# v0_9.net
KiCad netlist of a schematic drawn in EAGLE
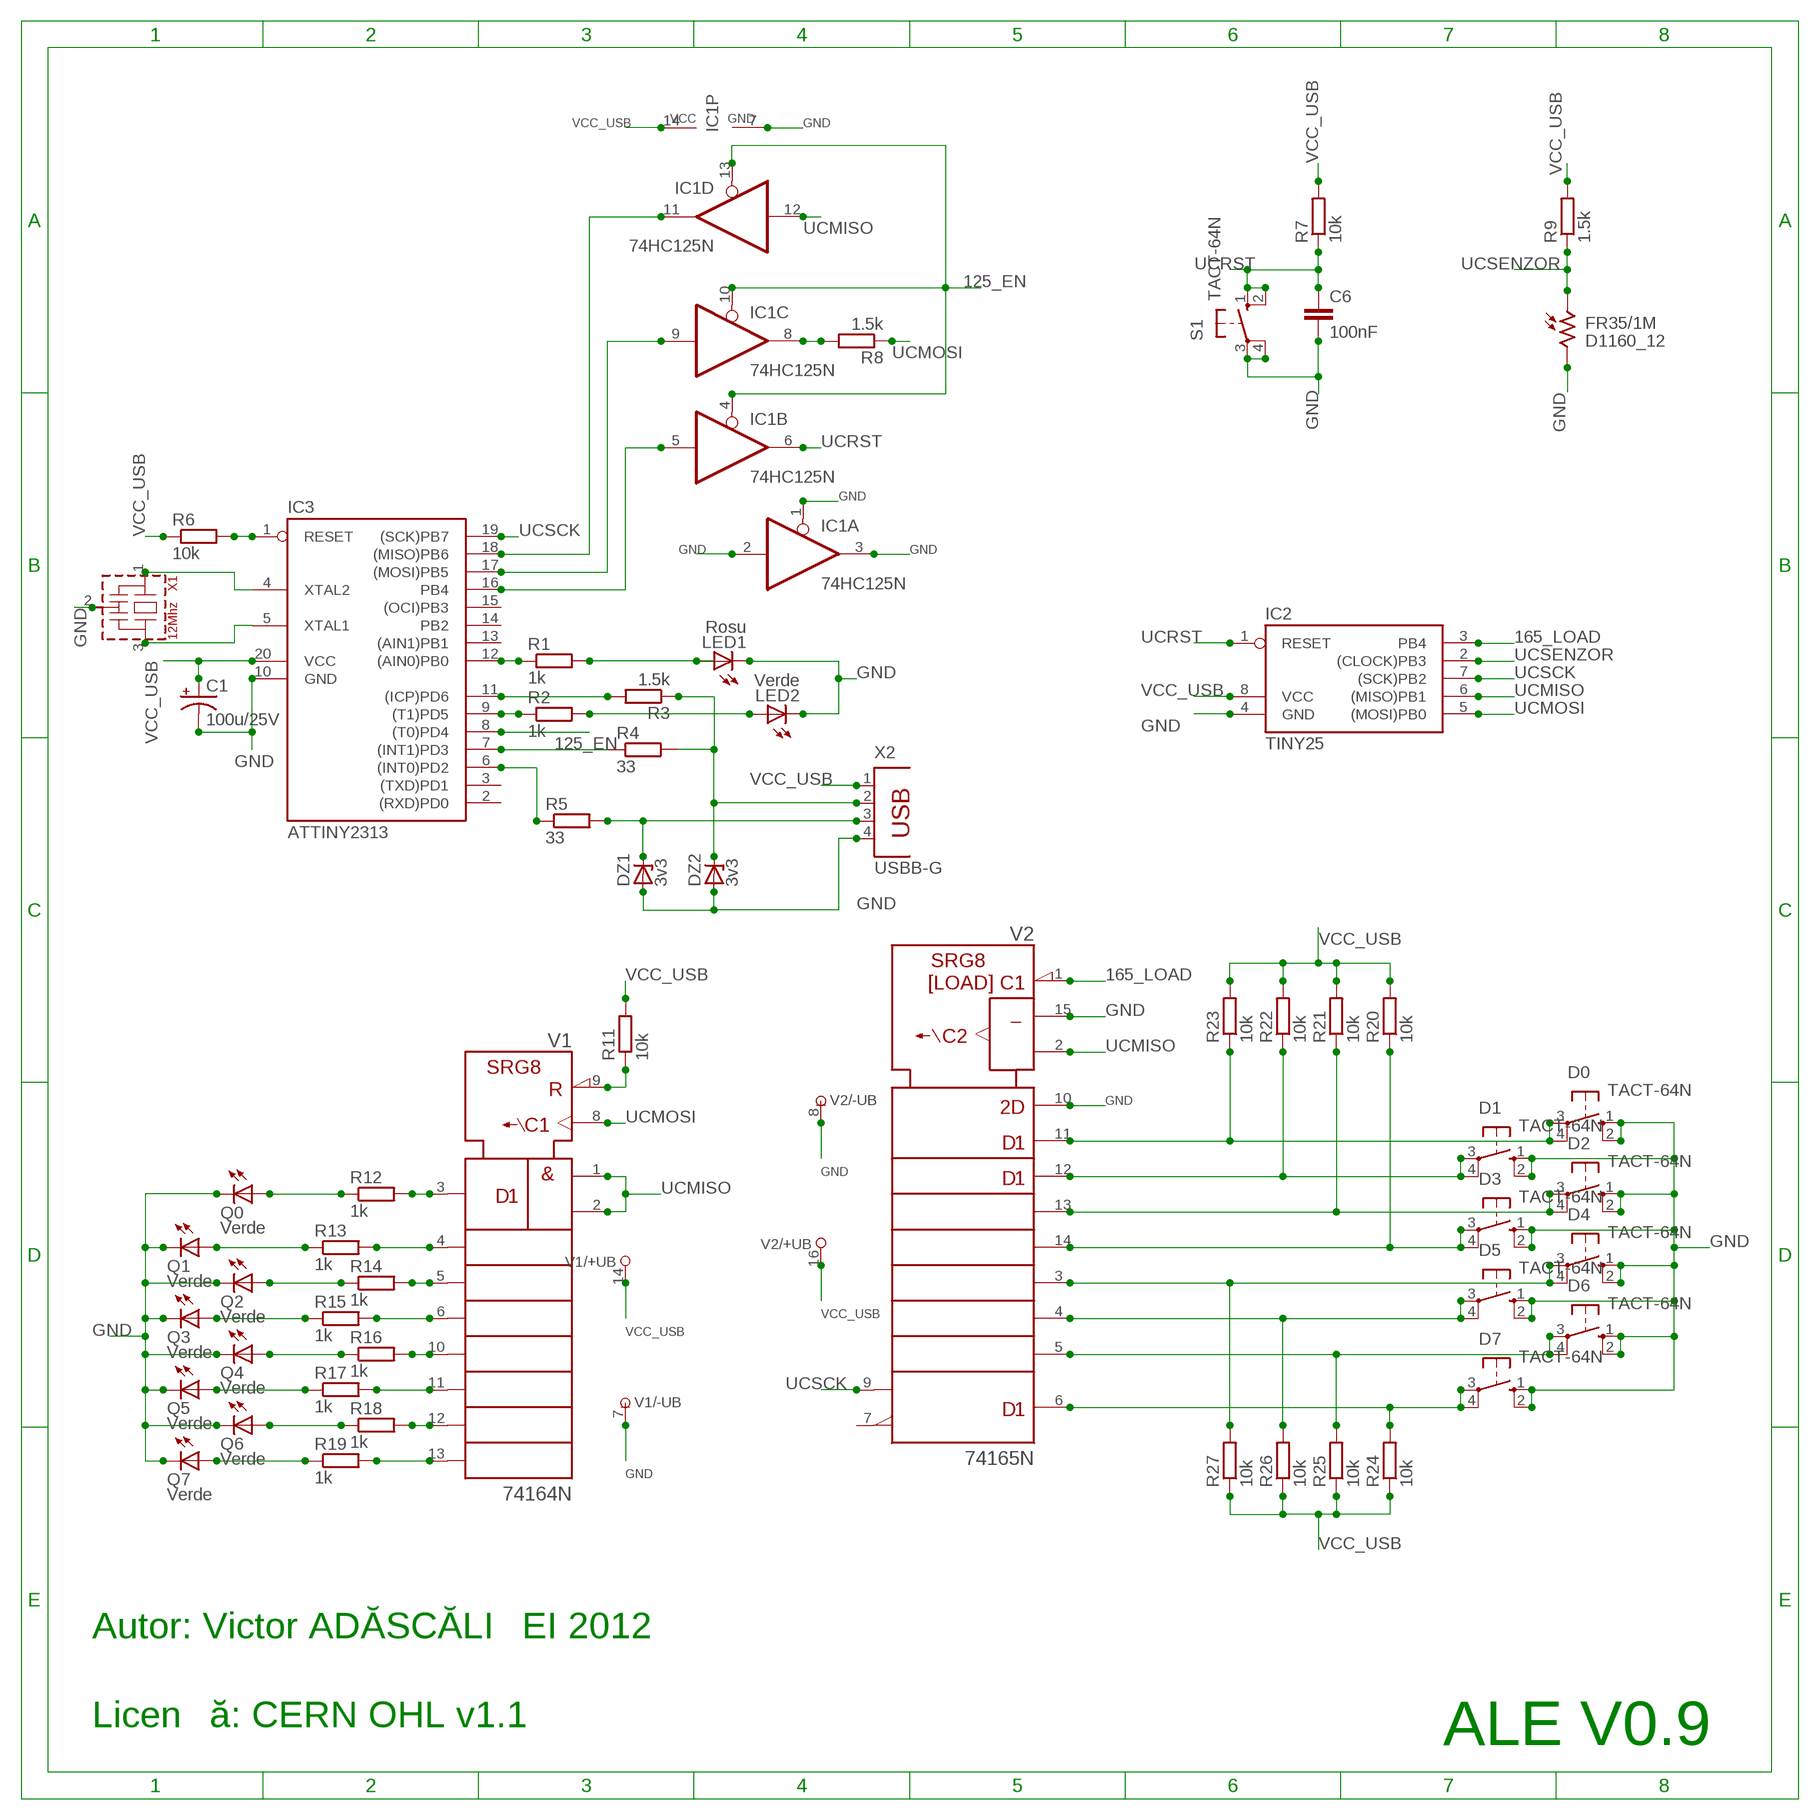
[diagram p0: schematic, sheet 1]

(export (version "E")
  (design (tool "Eeschema 10.0.6"))
  (components
    (comp (ref "C1")
      (value "100u/25V")
      (footprint "eagle-import:E2,5-6")
      (libsource (lib "eagle-import") (part "CPOL-USE2.5-6"))
    )
    (comp (ref "C6")
      (value "100nF")
      (footprint "eagle-import:C050-025X075")
      (libsource (lib "eagle-import") (part "C-EU050-025X075"))
    )
    (comp (ref "D0")
      (value "TACT-64N")
      (footprint "eagle-import:B3F-10XX")
      (libsource (lib "eagle-import") (part "10-XX"))
    )
    (comp (ref "D1")
      (value "TACT-64N")
      (footprint "eagle-import:B3F-10XX")
      (libsource (lib "eagle-import") (part "10-XX"))
    )
    (comp (ref "D2")
      (value "TACT-64N")
      (footprint "eagle-import:B3F-10XX")
      (libsource (lib "eagle-import") (part "10-XX"))
    )
    (comp (ref "D3")
      (value "TACT-64N")
      (footprint "eagle-import:B3F-10XX")
      (libsource (lib "eagle-import") (part "10-XX"))
    )
    (comp (ref "D4")
      (value "TACT-64N")
      (footprint "eagle-import:B3F-10XX")
      (libsource (lib "eagle-import") (part "10-XX"))
    )
    (comp (ref "D5")
      (value "TACT-64N")
      (footprint "eagle-import:B3F-10XX")
      (libsource (lib "eagle-import") (part "10-XX"))
    )
    (comp (ref "D6")
      (value "TACT-64N")
      (footprint "eagle-import:B3F-10XX")
      (libsource (lib "eagle-import") (part "10-XX"))
    )
    (comp (ref "D7")
      (value "TACT-64N")
      (footprint "eagle-import:B3F-10XX")
      (libsource (lib "eagle-import") (part "10-XX"))
    )
    (comp (ref "DZ1")
      (value "3v3")
      (footprint "eagle-import:ZDIO-7.5")
      (libsource (lib "eagle-import") (part "ZENER-DIODEZD-7.5"))
    )
    (comp (ref "DZ2")
      (value "3v3")
      (footprint "eagle-import:ZDIO-7.5")
      (libsource (lib "eagle-import") (part "ZENER-DIODEZD-7.5"))
    )
    (comp (ref "FR35/1M")
      (value "D1160_12")
      (footprint "eagle-import:D11XX")
      (libsource (lib "eagle-import") (part "D1160_12"))
    )
    (comp (ref "IC1")
      (value "74HC125N")
      (footprint "eagle-import:DIL14")
      (libsource (lib "eagle-import") (part "74125NAC"))
    )
    (comp (ref "IC2")
      (value "TINY25")
      (footprint "eagle-import:DIL08")
      (libsource (lib "eagle-import") (part "TINY22P"))
    )
    (comp (ref "IC3")
      (value "ATTINY2313")
      (footprint "eagle-import:DIL20")
      (libsource (lib "eagle-import") (part "AT90S2313P"))
    )
    (comp (ref "LED1")
      (value "Rosu")
      (footprint "eagle-import:LED3MM")
      (libsource (lib "eagle-import") (part "LED3MM"))
    )
    (comp (ref "LED2")
      (value "Verde")
      (footprint "eagle-import:LED3MM")
      (libsource (lib "eagle-import") (part "LED3MM"))
    )
    (comp (ref "Q0")
      (value "Verde")
      (footprint "eagle-import:LED3MM")
      (libsource (lib "eagle-import") (part "LED3MM"))
    )
    (comp (ref "Q1")
      (value "Verde")
      (footprint "eagle-import:LED3MM")
      (libsource (lib "eagle-import") (part "LED3MM"))
    )
    (comp (ref "Q2")
      (value "Verde")
      (footprint "eagle-import:LED3MM")
      (libsource (lib "eagle-import") (part "LED3MM"))
    )
    (comp (ref "Q3")
      (value "Verde")
      (footprint "eagle-import:LED3MM")
      (libsource (lib "eagle-import") (part "LED3MM"))
    )
    (comp (ref "Q4")
      (value "Verde")
      (footprint "eagle-import:LED3MM")
      (libsource (lib "eagle-import") (part "LED3MM"))
    )
    (comp (ref "Q5")
      (value "Verde")
      (footprint "eagle-import:LED3MM")
      (libsource (lib "eagle-import") (part "LED3MM"))
    )
    (comp (ref "Q6")
      (value "Verde")
      (footprint "eagle-import:LED3MM")
      (libsource (lib "eagle-import") (part "LED3MM"))
    )
    (comp (ref "Q7")
      (value "Verde")
      (footprint "eagle-import:LED3MM")
      (libsource (lib "eagle-import") (part "LED3MM"))
    )
    (comp (ref "R1")
      (value "1k")
      (footprint "eagle-import:0207_10")
      (libsource (lib "eagle-import") (part "R-EU_0207/10"))
    )
    (comp (ref "R2")
      (value "1k")
      (footprint "eagle-import:0204_5")
      (libsource (lib "eagle-import") (part "R-EU_0204/5"))
    )
    (comp (ref "R3")
      (value "1.5k")
      (footprint "eagle-import:0207_10")
      (libsource (lib "eagle-import") (part "R-EU_0207/10"))
    )
    (comp (ref "R4")
      (value "33")
      (footprint "eagle-import:0207_12")
      (libsource (lib "eagle-import") (part "R-EU_0207/12"))
    )
    (comp (ref "R5")
      (value "33")
      (footprint "eagle-import:0207_10")
      (libsource (lib "eagle-import") (part "R-EU_0207/10"))
    )
    (comp (ref "R6")
      (value "10k")
      (footprint "eagle-import:0207_10")
      (libsource (lib "eagle-import") (part "R-EU_0207/10"))
    )
    (comp (ref "R7")
      (value "10k")
      (footprint "eagle-import:0204_7")
      (libsource (lib "eagle-import") (part "R-EU_0204/7"))
    )
    (comp (ref "R8")
      (value "1.5k")
      (footprint "eagle-import:0207_10")
      (libsource (lib "eagle-import") (part "R-EU_0207/10"))
    )
    (comp (ref "R9")
      (value "1.5k")
      (footprint "eagle-import:0207_12")
      (libsource (lib "eagle-import") (part "R-EU_0207/12"))
    )
    (comp (ref "R11")
      (value "10k")
      (footprint "eagle-import:0207_15")
      (libsource (lib "eagle-import") (part "R-EU_0207/15"))
    )
    (comp (ref "R12")
      (value "1k")
      (footprint "eagle-import:0207_10")
      (libsource (lib "eagle-import") (part "R-EU_0207/10"))
    )
    (comp (ref "R13")
      (value "1k")
      (footprint "eagle-import:0207_10")
      (libsource (lib "eagle-import") (part "R-EU_0207/10"))
    )
    (comp (ref "R14")
      (value "1k")
      (footprint "eagle-import:0207_10")
      (libsource (lib "eagle-import") (part "R-EU_0207/10"))
    )
    (comp (ref "R15")
      (value "1k")
      (footprint "eagle-import:0207_10")
      (libsource (lib "eagle-import") (part "R-EU_0207/10"))
    )
    (comp (ref "R16")
      (value "1k")
      (footprint "eagle-import:0207_10")
      (libsource (lib "eagle-import") (part "R-EU_0207/10"))
    )
    (comp (ref "R17")
      (value "1k")
      (footprint "eagle-import:0207_10")
      (libsource (lib "eagle-import") (part "R-EU_0207/10"))
    )
    (comp (ref "R18")
      (value "1k")
      (footprint "eagle-import:0207_10")
      (libsource (lib "eagle-import") (part "R-EU_0207/10"))
    )
    (comp (ref "R19")
      (value "1k")
      (footprint "eagle-import:0207_10")
      (libsource (lib "eagle-import") (part "R-EU_0207/10"))
    )
    (comp (ref "R20")
      (value "10k")
      (footprint "eagle-import:0207_10")
      (libsource (lib "eagle-import") (part "R-EU_0207/10"))
    )
    (comp (ref "R21")
      (value "10k")
      (footprint "eagle-import:0207_10")
      (libsource (lib "eagle-import") (part "R-EU_0207/10"))
    )
    (comp (ref "R22")
      (value "10k")
      (footprint "eagle-import:0204_7")
      (libsource (lib "eagle-import") (part "R-EU_0204/7"))
    )
    (comp (ref "R23")
      (value "10k")
      (footprint "eagle-import:0204_7")
      (libsource (lib "eagle-import") (part "R-EU_0204/7"))
    )
    (comp (ref "R24")
      (value "10k")
      (footprint "eagle-import:0207_10")
      (libsource (lib "eagle-import") (part "R-EU_0207/10"))
    )
    (comp (ref "R25")
      (value "10k")
      (footprint "eagle-import:0207_10")
      (libsource (lib "eagle-import") (part "R-EU_0207/10"))
    )
    (comp (ref "R26")
      (value "10k")
      (footprint "eagle-import:0207_10")
      (libsource (lib "eagle-import") (part "R-EU_0207/10"))
    )
    (comp (ref "R27")
      (value "10k")
      (footprint "eagle-import:0207_10")
      (libsource (lib "eagle-import") (part "R-EU_0207/10"))
    )
    (comp (ref "S1")
      (value "TACT-64N")
      (footprint "eagle-import:B3F-10XX")
      (libsource (lib "eagle-import") (part "10-XX"))
    )
    (comp (ref "V1")
      (value "74164N")
      (footprint "eagle-import:DIL14")
      (libsource (lib "eagle-import") (part "74164N"))
    )
    (comp (ref "V2")
      (value "74165N")
      (footprint "eagle-import:DIL16")
      (libsource (lib "eagle-import") (part "74165N"))
    )
    (comp (ref "X1")
      (value "12Mhz")
      (footprint "eagle-import:CSTLS_X")
      (libsource (lib "eagle-import") (part "CSTLS_X"))
    )
    (comp (ref "X2")
      (value "USBB-G")
      (footprint "eagle-import:PN61729")
      (libsource (lib "eagle-import") (part "PN61729"))
    )
  )
  (nets
    (net (code "1") (name "/125_EN") (class "Default")
      (node (ref "IC1") (pin "10") (pinfunction "OE_10") (pintype "input"))
      (node (ref "IC1") (pin "13") (pinfunction "OE_13") (pintype "input"))
      (node (ref "IC1") (pin "4") (pinfunction "OE_4") (pintype "input"))
      (node (ref "IC3") (pin "8") (pinfunction "(T0)PD4_8") (pintype "bidirectional"))
    )
    (net (code "2") (name "/165_LOAD") (class "Default")
      (node (ref "IC2") (pin "3") (pinfunction "PB4_3") (pintype "bidirectional"))
      (node (ref "V2") (pin "1") (pinfunction "SH/~{LD}_1") (pintype "input"))
    )
    (net (code "3") (name "/GND") (class "Default")
      (node (ref "C1") (pin "-") (pinfunction "-_-") (pintype "passive"))
      (node (ref "C6") (pin "2") (pinfunction "2_2") (pintype "passive"))
      (node (ref "D0") (pin "1") (pinfunction "S_1") (pintype "passive"))
      (node (ref "D0") (pin "2") (pinfunction "S1_2") (pintype "passive"))
      (node (ref "D1") (pin "1") (pinfunction "S_1") (pintype "passive"))
      (node (ref "D1") (pin "2") (pinfunction "S1_2") (pintype "passive"))
      (node (ref "D2") (pin "1") (pinfunction "S_1") (pintype "passive"))
      (node (ref "D2") (pin "2") (pinfunction "S1_2") (pintype "passive"))
      (node (ref "D3") (pin "1") (pinfunction "S_1") (pintype "passive"))
      (node (ref "D3") (pin "2") (pinfunction "S1_2") (pintype "passive"))
      (node (ref "D4") (pin "1") (pinfunction "S_1") (pintype "passive"))
      (node (ref "D4") (pin "2") (pinfunction "S1_2") (pintype "passive"))
      (node (ref "D5") (pin "1") (pinfunction "S_1") (pintype "passive"))
      (node (ref "D5") (pin "2") (pinfunction "S1_2") (pintype "passive"))
      (node (ref "D6") (pin "1") (pinfunction "S_1") (pintype "passive"))
      (node (ref "D6") (pin "2") (pinfunction "S1_2") (pintype "passive"))
      (node (ref "D7") (pin "1") (pinfunction "S_1") (pintype "passive"))
      (node (ref "D7") (pin "2") (pinfunction "S1_2") (pintype "passive"))
      (node (ref "DZ1") (pin "A") (pinfunction "A_A") (pintype "passive"))
      (node (ref "DZ2") (pin "A") (pinfunction "A_A") (pintype "passive"))
      (node (ref "FR35/1M") (pin "2") (pinfunction "2_2") (pintype "passive"))
      (node (ref "IC1") (pin "1") (pinfunction "OE_1") (pintype "input"))
      (node (ref "IC1") (pin "2") (pinfunction "I_2") (pintype "input"))
      (node (ref "IC1") (pin "3") (pinfunction "O_3") (pintype "tri_state"))
      (node (ref "IC1") (pin "7") (pinfunction "GND_7") (pintype "power_in"))
      (node (ref "IC2") (pin "4") (pinfunction "GND_4") (pintype "power_in"))
      (node (ref "IC3") (pin "10") (pinfunction "GND_10") (pintype "power_in"))
      (node (ref "LED1") (pin "K") (pinfunction "C_K") (pintype "passive"))
      (node (ref "LED2") (pin "K") (pinfunction "C_K") (pintype "passive"))
      (node (ref "Q0") (pin "K") (pinfunction "C_K") (pintype "passive"))
      (node (ref "Q1") (pin "K") (pinfunction "C_K") (pintype "passive"))
      (node (ref "Q2") (pin "K") (pinfunction "C_K") (pintype "passive"))
      (node (ref "Q3") (pin "K") (pinfunction "C_K") (pintype "passive"))
      (node (ref "Q4") (pin "K") (pinfunction "C_K") (pintype "passive"))
      (node (ref "Q5") (pin "K") (pinfunction "C_K") (pintype "passive"))
      (node (ref "Q6") (pin "K") (pinfunction "C_K") (pintype "passive"))
      (node (ref "Q7") (pin "K") (pinfunction "C_K") (pintype "passive"))
      (node (ref "S1") (pin "3") (pinfunction "P_3") (pintype "passive"))
      (node (ref "S1") (pin "4") (pinfunction "P1_4") (pintype "passive"))
      (node (ref "V1") (pin "7") (pinfunction "-UB_7") (pintype "power_in"))
      (node (ref "V2") (pin "10") (pinfunction "SER_10") (pintype "input"))
      (node (ref "V2") (pin "15") (pinfunction "CLK_INH_15") (pintype "input"))
      (node (ref "V2") (pin "8") (pinfunction "-UB_8") (pintype "power_in"))
      (node (ref "X1") (pin "2") (pinfunction "VSS_2") (pintype "power_in"))
      (node (ref "X2") (pin "4") (pinfunction "4_4") (pintype "passive"))
    )
    (net (code "4") (name "/UCMISO") (class "Default")
      (node (ref "IC1") (pin "12") (pinfunction "I_12") (pintype "input"))
      (node (ref "IC2") (pin "6") (pinfunction "(MISO)PB1_6") (pintype "bidirectional"))
      (node (ref "V1") (pin "1") (pinfunction "A_1") (pintype "input"))
      (node (ref "V1") (pin "2") (pinfunction "B_2") (pintype "input"))
      (node (ref "V2") (pin "2") (pinfunction "CLK_2") (pintype "input"))
    )
    (net (code "5") (name "/UCMOSI") (class "Default")
      (node (ref "IC2") (pin "5") (pinfunction "(MOSI)PB0_5") (pintype "bidirectional"))
      (node (ref "R8") (pin "1") (pinfunction "1_1") (pintype "passive"))
      (node (ref "V1") (pin "8") (pinfunction "CLK_8") (pintype "input"))
    )
    (net (code "6") (name "/UCRST") (class "Default")
      (node (ref "C6") (pin "1") (pinfunction "1_1") (pintype "passive"))
      (node (ref "IC1") (pin "6") (pinfunction "O_6") (pintype "tri_state"))
      (node (ref "IC2") (pin "1") (pinfunction "RESET_1") (pintype "input"))
      (node (ref "R7") (pin "1") (pinfunction "1_1") (pintype "passive"))
      (node (ref "S1") (pin "1") (pinfunction "S_1") (pintype "passive"))
      (node (ref "S1") (pin "2") (pinfunction "S1_2") (pintype "passive"))
    )
    (net (code "7") (name "/UCSCK") (class "Default")
      (node (ref "IC2") (pin "7") (pinfunction "(SCK)PB2_7") (pintype "bidirectional"))
      (node (ref "IC3") (pin "19") (pinfunction "(SCK)PB7_19") (pintype "bidirectional"))
      (node (ref "V2") (pin "9") (pinfunction "QH_9") (pintype "output"))
    )
    (net (code "8") (name "/UCSENZOR") (class "Default")
      (node (ref "FR35/1M") (pin "1") (pinfunction "1_1") (pintype "passive"))
      (node (ref "IC2") (pin "2") (pinfunction "(CLOCK)PB3_2") (pintype "bidirectional"))
      (node (ref "R9") (pin "1") (pinfunction "1_1") (pintype "passive"))
    )
    (net (code "9") (name "/VCC_USB") (class "Default")
      (node (ref "C1") (pin "+") (pinfunction "+_+") (pintype "passive"))
      (node (ref "IC1") (pin "14") (pinfunction "VCC_14") (pintype "power_in"))
      (node (ref "IC2") (pin "8") (pinfunction "VCC_8") (pintype "power_in"))
      (node (ref "IC3") (pin "20") (pinfunction "VCC_20") (pintype "power_in"))
      (node (ref "R11") (pin "2") (pinfunction "2_2") (pintype "passive"))
      (node (ref "R20") (pin "2") (pinfunction "2_2") (pintype "passive"))
      (node (ref "R21") (pin "2") (pinfunction "2_2") (pintype "passive"))
      (node (ref "R22") (pin "2") (pinfunction "2_2") (pintype "passive"))
      (node (ref "R23") (pin "2") (pinfunction "2_2") (pintype "passive"))
      (node (ref "R24") (pin "1") (pinfunction "1_1") (pintype "passive"))
      (node (ref "R25") (pin "1") (pinfunction "1_1") (pintype "passive"))
      (node (ref "R26") (pin "1") (pinfunction "1_1") (pintype "passive"))
      (node (ref "R27") (pin "1") (pinfunction "1_1") (pintype "passive"))
      (node (ref "R6") (pin "1") (pinfunction "1_1") (pintype "passive"))
      (node (ref "R7") (pin "2") (pinfunction "2_2") (pintype "passive"))
      (node (ref "R9") (pin "2") (pinfunction "2_2") (pintype "passive"))
      (node (ref "V1") (pin "14") (pinfunction "+UB_14") (pintype "power_in"))
      (node (ref "V2") (pin "16") (pinfunction "+UB_16") (pintype "power_in"))
      (node (ref "X2") (pin "1") (pinfunction "1_1") (pintype "passive"))
    )
    (net (code "10") (name "Net-(D0-P)") (class "Default")
      (node (ref "D0") (pin "3") (pinfunction "P_3") (pintype "passive"))
      (node (ref "D0") (pin "4") (pinfunction "P1_4") (pintype "passive"))
      (node (ref "R23") (pin "1") (pinfunction "1_1") (pintype "passive"))
      (node (ref "V2") (pin "11") (pinfunction "A_11") (pintype "input"))
    )
    (net (code "11") (name "Net-(D1-P)") (class "Default")
      (node (ref "D1") (pin "3") (pinfunction "P_3") (pintype "passive"))
      (node (ref "D1") (pin "4") (pinfunction "P1_4") (pintype "passive"))
      (node (ref "R22") (pin "1") (pinfunction "1_1") (pintype "passive"))
      (node (ref "V2") (pin "12") (pinfunction "B_12") (pintype "input"))
    )
    (net (code "12") (name "Net-(D2-P)") (class "Default")
      (node (ref "D2") (pin "3") (pinfunction "P_3") (pintype "passive"))
      (node (ref "D2") (pin "4") (pinfunction "P1_4") (pintype "passive"))
      (node (ref "R21") (pin "1") (pinfunction "1_1") (pintype "passive"))
      (node (ref "V2") (pin "13") (pinfunction "C_13") (pintype "input"))
    )
    (net (code "13") (name "Net-(D3-P)") (class "Default")
      (node (ref "D3") (pin "3") (pinfunction "P_3") (pintype "passive"))
      (node (ref "D3") (pin "4") (pinfunction "P1_4") (pintype "passive"))
      (node (ref "R20") (pin "1") (pinfunction "1_1") (pintype "passive"))
      (node (ref "V2") (pin "14") (pinfunction "D_14") (pintype "input"))
    )
    (net (code "14") (name "Net-(D4-P)") (class "Default")
      (node (ref "D4") (pin "3") (pinfunction "P_3") (pintype "passive"))
      (node (ref "D4") (pin "4") (pinfunction "P1_4") (pintype "passive"))
      (node (ref "R27") (pin "2") (pinfunction "2_2") (pintype "passive"))
      (node (ref "V2") (pin "3") (pinfunction "E_3") (pintype "input"))
    )
    (net (code "15") (name "Net-(D5-P)") (class "Default")
      (node (ref "D5") (pin "3") (pinfunction "P_3") (pintype "passive"))
      (node (ref "D5") (pin "4") (pinfunction "P1_4") (pintype "passive"))
      (node (ref "R26") (pin "2") (pinfunction "2_2") (pintype "passive"))
      (node (ref "V2") (pin "4") (pinfunction "F_4") (pintype "input"))
    )
    (net (code "16") (name "Net-(D6-P)") (class "Default")
      (node (ref "D6") (pin "3") (pinfunction "P_3") (pintype "passive"))
      (node (ref "D6") (pin "4") (pinfunction "P1_4") (pintype "passive"))
      (node (ref "R25") (pin "2") (pinfunction "2_2") (pintype "passive"))
      (node (ref "V2") (pin "5") (pinfunction "G_5") (pintype "input"))
    )
    (net (code "17") (name "Net-(D7-P)") (class "Default")
      (node (ref "D7") (pin "3") (pinfunction "P_3") (pintype "passive"))
      (node (ref "D7") (pin "4") (pinfunction "P1_4") (pintype "passive"))
      (node (ref "R24") (pin "2") (pinfunction "2_2") (pintype "passive"))
      (node (ref "V2") (pin "6") (pinfunction "H_6") (pintype "input"))
    )
    (net (code "18") (name "Net-(DZ1-PadC)") (class "Default")
      (node (ref "DZ1") (pin "C") (pinfunction "C_C") (pintype "passive"))
      (node (ref "R5") (pin "2") (pinfunction "2_2") (pintype "passive"))
      (node (ref "X2") (pin "3") (pinfunction "3_3") (pintype "passive"))
    )
    (net (code "19") (name "Net-(DZ2-PadC)") (class "Default")
      (node (ref "DZ2") (pin "C") (pinfunction "C_C") (pintype "passive"))
      (node (ref "R3") (pin "1") (pinfunction "1_1") (pintype "passive"))
      (node (ref "R4") (pin "2") (pinfunction "2_2") (pintype "passive"))
      (node (ref "X2") (pin "2") (pinfunction "2_2") (pintype "passive"))
    )
    (net (code "20") (name "Net-(IC1B-I)") (class "Default")
      (node (ref "IC1") (pin "5") (pinfunction "I_5") (pintype "input"))
      (node (ref "IC3") (pin "16") (pinfunction "PB4_16") (pintype "bidirectional"))
    )
    (net (code "21") (name "Net-(IC1C-I)") (class "Default")
      (node (ref "IC1") (pin "9") (pinfunction "I_9") (pintype "input"))
      (node (ref "IC3") (pin "17") (pinfunction "(MOSI)PB5_17") (pintype "bidirectional"))
    )
    (net (code "22") (name "Net-(IC1C-O)") (class "Default")
      (node (ref "IC1") (pin "8") (pinfunction "O_8") (pintype "tri_state"))
      (node (ref "R8") (pin "2") (pinfunction "2_2") (pintype "passive"))
    )
    (net (code "23") (name "Net-(IC1D-O)") (class "Default")
      (node (ref "IC1") (pin "11") (pinfunction "O_11") (pintype "tri_state"))
      (node (ref "IC3") (pin "18") (pinfunction "(MISO)PB6_18") (pintype "bidirectional"))
    )
    (net (code "24") (name "Net-(IC3-(AIN0)PB0)") (class "Default")
      (node (ref "IC3") (pin "12") (pinfunction "(AIN0)PB0_12") (pintype "bidirectional"))
      (node (ref "R1") (pin "1") (pinfunction "1_1") (pintype "passive"))
    )
    (net (code "25") (name "Net-(IC3-(ICP)PD6)") (class "Default")
      (node (ref "IC3") (pin "11") (pinfunction "(ICP)PD6_11") (pintype "bidirectional"))
      (node (ref "R3") (pin "2") (pinfunction "2_2") (pintype "passive"))
    )
    (net (code "26") (name "Net-(IC3-(INT0)PD2)") (class "Default")
      (node (ref "IC3") (pin "6") (pinfunction "(INT0)PD2_6") (pintype "bidirectional"))
      (node (ref "R5") (pin "1") (pinfunction "1_1") (pintype "passive"))
    )
    (net (code "27") (name "Net-(IC3-(INT1)PD3)") (class "Default")
      (node (ref "IC3") (pin "7") (pinfunction "(INT1)PD3_7") (pintype "bidirectional"))
      (node (ref "R4") (pin "1") (pinfunction "1_1") (pintype "passive"))
    )
    (net (code "28") (name "Net-(IC3-(T1)PD5)") (class "Default")
      (node (ref "IC3") (pin "9") (pinfunction "(T1)PD5_9") (pintype "bidirectional"))
      (node (ref "R2") (pin "1") (pinfunction "1_1") (pintype "passive"))
    )
    (net (code "29") (name "Net-(IC3-RESET)") (class "Default")
      (node (ref "IC3") (pin "1") (pinfunction "RESET_1") (pintype "bidirectional"))
      (node (ref "R6") (pin "2") (pinfunction "2_2") (pintype "passive"))
    )
    (net (code "30") (name "Net-(IC3-XTAL1)") (class "Default")
      (node (ref "IC3") (pin "5") (pinfunction "XTAL1_5") (pintype "bidirectional"))
      (node (ref "X1") (pin "3") (pinfunction "3_3") (pintype "input"))
    )
    (net (code "31") (name "Net-(IC3-XTAL2)") (class "Default")
      (node (ref "IC3") (pin "4") (pinfunction "XTAL2_4") (pintype "bidirectional"))
      (node (ref "X1") (pin "1") (pinfunction "1_1") (pintype "output"))
    )
    (net (code "32") (name "Net-(LED1-PadA)") (class "Default")
      (node (ref "LED1") (pin "A") (pinfunction "A_A") (pintype "passive"))
      (node (ref "R1") (pin "2") (pinfunction "2_2") (pintype "passive"))
    )
    (net (code "33") (name "Net-(LED2-PadA)") (class "Default")
      (node (ref "LED2") (pin "A") (pinfunction "A_A") (pintype "passive"))
      (node (ref "R2") (pin "2") (pinfunction "2_2") (pintype "passive"))
    )
    (net (code "34") (name "Net-(Q0-PadA)") (class "Default")
      (node (ref "Q0") (pin "A") (pinfunction "A_A") (pintype "passive"))
      (node (ref "R12") (pin "1") (pinfunction "1_1") (pintype "passive"))
    )
    (net (code "35") (name "Net-(Q1-PadA)") (class "Default")
      (node (ref "Q1") (pin "A") (pinfunction "A_A") (pintype "passive"))
      (node (ref "R13") (pin "1") (pinfunction "1_1") (pintype "passive"))
    )
    (net (code "36") (name "Net-(Q2-PadA)") (class "Default")
      (node (ref "Q2") (pin "A") (pinfunction "A_A") (pintype "passive"))
      (node (ref "R14") (pin "1") (pinfunction "1_1") (pintype "passive"))
    )
    (net (code "37") (name "Net-(Q3-PadA)") (class "Default")
      (node (ref "Q3") (pin "A") (pinfunction "A_A") (pintype "passive"))
      (node (ref "R15") (pin "1") (pinfunction "1_1") (pintype "passive"))
    )
    (net (code "38") (name "Net-(Q4-PadA)") (class "Default")
      (node (ref "Q4") (pin "A") (pinfunction "A_A") (pintype "passive"))
      (node (ref "R16") (pin "1") (pinfunction "1_1") (pintype "passive"))
    )
    (net (code "39") (name "Net-(Q5-PadA)") (class "Default")
      (node (ref "Q5") (pin "A") (pinfunction "A_A") (pintype "passive"))
      (node (ref "R17") (pin "1") (pinfunction "1_1") (pintype "passive"))
    )
    (net (code "40") (name "Net-(Q6-PadA)") (class "Default")
      (node (ref "Q6") (pin "A") (pinfunction "A_A") (pintype "passive"))
      (node (ref "R18") (pin "1") (pinfunction "1_1") (pintype "passive"))
    )
    (net (code "41") (name "Net-(Q7-PadA)") (class "Default")
      (node (ref "Q7") (pin "A") (pinfunction "A_A") (pintype "passive"))
      (node (ref "R19") (pin "1") (pinfunction "1_1") (pintype "passive"))
    )
    (net (code "42") (name "Net-(V1C-QA)") (class "Default")
      (node (ref "R12") (pin "2") (pinfunction "2_2") (pintype "passive"))
      (node (ref "V1") (pin "3") (pinfunction "QA_3") (pintype "output"))
    )
    (net (code "43") (name "Net-(V1C-QB)") (class "Default")
      (node (ref "R13") (pin "2") (pinfunction "2_2") (pintype "passive"))
      (node (ref "V1") (pin "4") (pinfunction "QB_4") (pintype "output"))
    )
    (net (code "44") (name "Net-(V1C-QC)") (class "Default")
      (node (ref "R14") (pin "2") (pinfunction "2_2") (pintype "passive"))
      (node (ref "V1") (pin "5") (pinfunction "QC_5") (pintype "output"))
    )
    (net (code "45") (name "Net-(V1C-QD)") (class "Default")
      (node (ref "R15") (pin "2") (pinfunction "2_2") (pintype "passive"))
      (node (ref "V1") (pin "6") (pinfunction "QD_6") (pintype "output"))
    )
    (net (code "46") (name "Net-(V1C-QE)") (class "Default")
      (node (ref "R16") (pin "2") (pinfunction "2_2") (pintype "passive"))
      (node (ref "V1") (pin "10") (pinfunction "QE_10") (pintype "output"))
    )
    (net (code "47") (name "Net-(V1C-QF)") (class "Default")
      (node (ref "R17") (pin "2") (pinfunction "2_2") (pintype "passive"))
      (node (ref "V1") (pin "11") (pinfunction "QF_11") (pintype "output"))
    )
    (net (code "48") (name "Net-(V1C-QG)") (class "Default")
      (node (ref "R18") (pin "2") (pinfunction "2_2") (pintype "passive"))
      (node (ref "V1") (pin "12") (pinfunction "QG_12") (pintype "output"))
    )
    (net (code "49") (name "Net-(V1C-QH)") (class "Default")
      (node (ref "R19") (pin "2") (pinfunction "2_2") (pintype "passive"))
      (node (ref "V1") (pin "13") (pinfunction "QH_13") (pintype "output"))
    )
    (net (code "50") (name "Net-(V1C-~{CLR})") (class "Default")
      (node (ref "R11") (pin "1") (pinfunction "1_1") (pintype "passive"))
      (node (ref "V1") (pin "9") (pinfunction "~{CLR}_9") (pintype "input"))
    )
    (net (code "51") (name "unconnected-(IC3-(AIN1)PB1-Pad13)") (class "Default")
      (node (ref "IC3") (pin "13") (pinfunction "(AIN1)PB1_13") (pintype "bidirectional"))
    )
    (net (code "52") (name "unconnected-(IC3-(OCI)PB3-Pad15)") (class "Default")
      (node (ref "IC3") (pin "15") (pinfunction "(OCI)PB3_15") (pintype "bidirectional"))
    )
    (net (code "53") (name "unconnected-(IC3-(RXD)PD0-Pad2)") (class "Default")
      (node (ref "IC3") (pin "2") (pinfunction "(RXD)PD0_2") (pintype "bidirectional"))
    )
    (net (code "54") (name "unconnected-(IC3-(TXD)PD1-Pad3)") (class "Default")
      (node (ref "IC3") (pin "3") (pinfunction "(TXD)PD1_3") (pintype "bidirectional"))
    )
    (net (code "55") (name "unconnected-(IC3-PB2-Pad14)") (class "Default")
      (node (ref "IC3") (pin "14") (pinfunction "PB2_14") (pintype "bidirectional"))
    )
    (net (code "56") (name "unconnected-(V2C-~{QH}-Pad7)") (class "Default")
      (node (ref "V2") (pin "7") (pinfunction "~{QH}_7") (pintype "output"))
    )
  )
)
